# Horn_Board_Rev_1.net
KiCad netlist of a schematic drawn in EAGLE
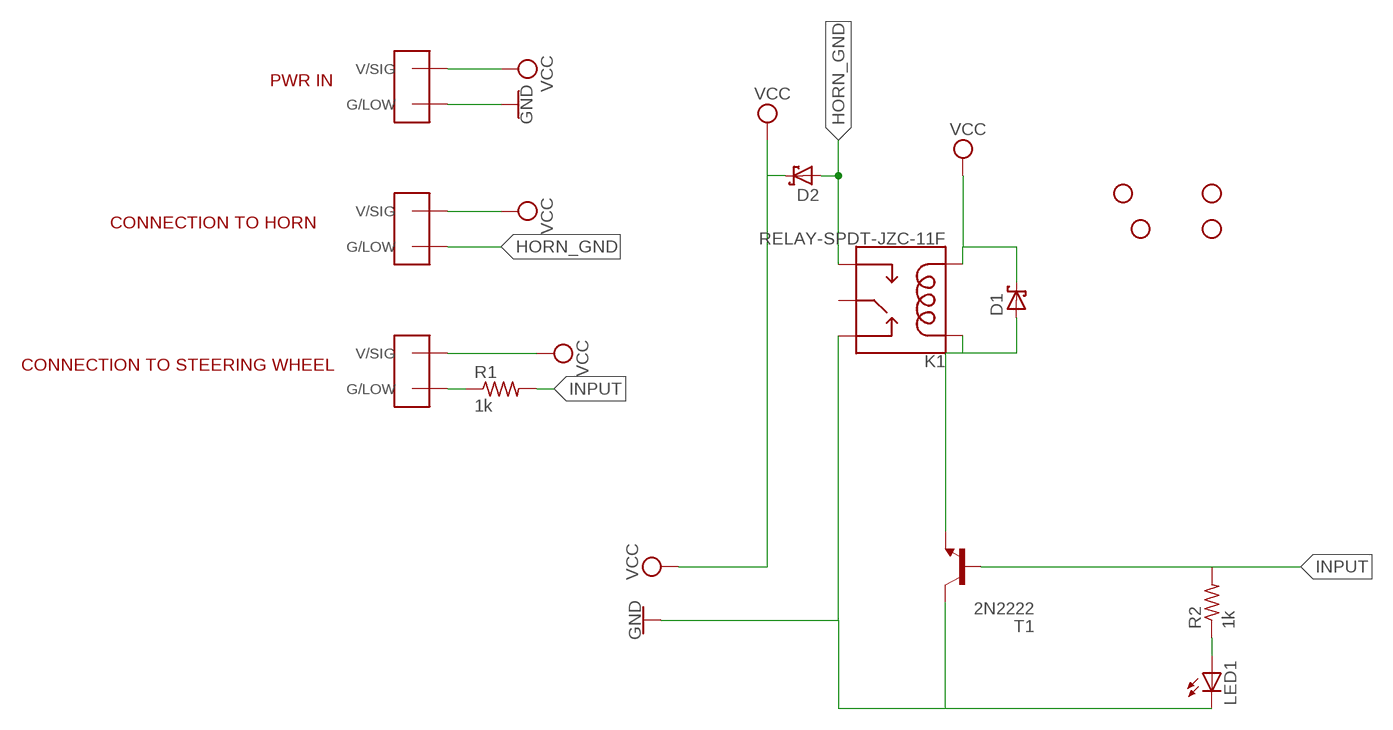
[diagram p0: schematic, sheet 1]

(export (version "E")
  (design (tool "Eeschema 10.0.6"))
  (components
    (comp (ref "D1")
      (value "SCHOTTKY-DIODEAG")
      (footprint "eagle-import:AG")
      (libsource (lib "eagle-import") (part "SCHOTTKY-DIODEAG"))
    )
    (comp (ref "D2")
      (value "SCHOTTKY-DIODEAG")
      (footprint "eagle-import:AG")
      (libsource (lib "eagle-import") (part "SCHOTTKY-DIODEAG"))
    )
    (comp (ref "H1")
      (value "STAND-OFF")
      (footprint "eagle-import:STAND-OFF")
      (libsource (lib "eagle-import") (part "STAND-OFF"))
    )
    (comp (ref "H2")
      (value "STAND-OFF")
      (footprint "eagle-import:STAND-OFF")
      (libsource (lib "eagle-import") (part "STAND-OFF"))
    )
    (comp (ref "H3")
      (value "STAND-OFF")
      (footprint "eagle-import:STAND-OFF")
      (libsource (lib "eagle-import") (part "STAND-OFF"))
    )
    (comp (ref "H4")
      (value "STAND-OFF")
      (footprint "eagle-import:STAND-OFF")
      (libsource (lib "eagle-import") (part "STAND-OFF"))
    )
    (comp (ref "K1")
      (value "RELAY-SPDT-JZC-11F")
      (footprint "eagle-import:RELAY-JZC")
      (libsource (lib "eagle-import") (part "RELAY-SPDT-JZC-11F"))
    )
    (comp (ref "LED1")
      (value "LED")
      (footprint "eagle-import:SMARTLED-TTW")
      (libsource (lib "eagle-import") (part "LED"))
    )
    (comp (ref "R1")
      (value "1k")
      (footprint "eagle-import:0204V")
      (libsource (lib "eagle-import") (part "R-US_0204/2V"))
    )
    (comp (ref "R2")
      (value "1k")
      (footprint "eagle-import:0204V")
      (libsource (lib "eagle-import") (part "R-US_0204/2V"))
    )
    (comp (ref "T1")
      (value "2N2222")
      (footprint "eagle-import:TO92-EBC-OVAL")
      (libsource (lib "eagle-import") (part "2N2222"))
    )
    (comp (ref "U$1")
      (value "TE770966")
      (footprint "eagle-import:2X1-MATE-N-LOCK")
      (libsource (lib "eagle-import") (part "TE770966"))
    )
    (comp (ref "U$2")
      (value "TE770966")
      (footprint "eagle-import:2X1-MATE-N-LOCK")
      (libsource (lib "eagle-import") (part "TE770966"))
    )
    (comp (ref "U$8")
      (value "TE770966")
      (footprint "eagle-import:2X1-MATE-N-LOCK")
      (libsource (lib "eagle-import") (part "TE770966"))
    )
  )
  (nets
    (net (code "1") (name "GND") (class "Default")
      (node (ref "K1") (pin "2") (pinfunction "NC_2") (pintype "bidirectional"))
      (node (ref "LED1") (pin "C@1") (pinfunction "C_C@1") (pintype "passive"))
      (node (ref "T1") (pin "C") (pinfunction "C_C") (pintype "passive"))
      (node (ref "U$8") (pin "CIRCUIT2") (pinfunction "G/LOW_CIRCUIT2") (pintype "bidirectional"))
    )
    (net (code "2") (name "HORN_GND") (class "Default")
      (node (ref "D2") (pin "A") (pinfunction "A_A") (pintype "passive"))
      (node (ref "K1") (pin "3") (pinfunction "NO_3") (pintype "bidirectional"))
      (node (ref "U$1") (pin "CIRCUIT2") (pinfunction "G/LOW_CIRCUIT2") (pintype "bidirectional"))
    )
    (net (code "3") (name "INPUT") (class "Default")
      (node (ref "R1") (pin "2") (pinfunction "2_2") (pintype "passive"))
      (node (ref "R2") (pin "2") (pinfunction "2_2") (pintype "passive"))
      (node (ref "T1") (pin "B") (pinfunction "B_B") (pintype "passive"))
    )
    (net (code "4") (name "Net-(K1-COIL1)") (class "Default")
      (node (ref "D1") (pin "A") (pinfunction "A_A") (pintype "passive"))
      (node (ref "K1") (pin "5") (pinfunction "COIL1_5") (pintype "bidirectional"))
      (node (ref "T1") (pin "E") (pinfunction "E_E") (pintype "passive"))
    )
    (net (code "5") (name "Net-(LED1-A)") (class "Default")
      (node (ref "LED1") (pin "A@1") (pinfunction "A_A@1") (pintype "passive"))
      (node (ref "R2") (pin "1") (pinfunction "1_1") (pintype "passive"))
    )
    (net (code "6") (name "Net-(U$2-G{slash}LOW)") (class "Default")
      (node (ref "R1") (pin "1") (pinfunction "1_1") (pintype "passive"))
      (node (ref "U$2") (pin "CIRCUIT2") (pinfunction "G/LOW_CIRCUIT2") (pintype "bidirectional"))
    )
    (net (code "7") (name "VCC") (class "Default")
      (node (ref "D1") (pin "C") (pinfunction "C_C") (pintype "passive"))
      (node (ref "D2") (pin "C") (pinfunction "C_C") (pintype "passive"))
      (node (ref "K1") (pin "1") (pinfunction "COIL2_1") (pintype "bidirectional"))
      (node (ref "U$1") (pin "CIRCUIT1") (pinfunction "V/SIG_CIRCUIT1") (pintype "bidirectional"))
      (node (ref "U$2") (pin "CIRCUIT1") (pinfunction "V/SIG_CIRCUIT1") (pintype "bidirectional"))
      (node (ref "U$8") (pin "CIRCUIT1") (pinfunction "V/SIG_CIRCUIT1") (pintype "bidirectional"))
    )
    (net (code "8") (name "unconnected-(K1-MAIN-Pad4)") (class "Default")
      (node (ref "K1") (pin "4") (pinfunction "MAIN_4") (pintype "bidirectional"))
    )
  )
)
